# OnePhase_MainPower.net
KiCad netlist of a schematic drawn in Altium Designer
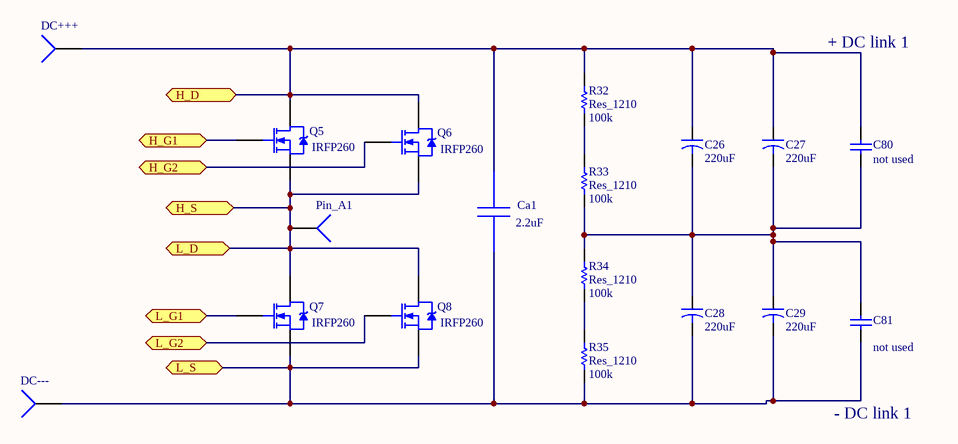
[diagram p0: OnePhase_MainPower.SchDoc]

(export (version "E")
  (design (tool "Eeschema 10.0.6"))
  (components
    (comp (ref "C26")
      (value "220uF")
      (footprint "Capacitor Eletrolitico - duplicate")
      (description "Capacitor")
      (fields (field (name "Comment") "Cap2"))
      (libsource (lib "Miscellaneous Devices") (part "Cap2"))
    )
    (comp (ref "C27")
      (value "220uF")
      (footprint "Capacitor Eletrolitico - duplicate")
      (description "Capacitor")
      (fields (field (name "Comment") "Cap2"))
      (libsource (lib "Miscellaneous Devices") (part "Cap2"))
    )
    (comp (ref "C28")
      (value "220uF")
      (footprint "Capacitor Eletrolitico - duplicate")
      (description "Capacitor")
      (fields (field (name "Comment") "Cap2"))
      (libsource (lib "Miscellaneous Devices") (part "Cap2"))
    )
    (comp (ref "C29")
      (value "220uF")
      (footprint "Capacitor Eletrolitico - duplicate")
      (description "Capacitor")
      (fields (field (name "Comment") "Cap2"))
      (libsource (lib "Miscellaneous Devices") (part "Cap2"))
    )
    (comp (ref "C80")
      (value "not used")
      (footprint "Capacitor_Pol_15x6mm")
      (description "Capacitor")
      (libsource (lib "Miscellaneous Devices") (part "Cap"))
    )
    (comp (ref "C81")
      (value "not used")
      (footprint "Capacitor_Pol_15x6mm")
      (description "Capacitor")
      (libsource (lib "Miscellaneous Devices") (part "Cap"))
    )
    (comp (ref "Ca1")
      (value "2.2uF")
      (footprint "Capacitor_Pol_2Sizes")
      (description "GRM21BC81E475KA1")
      (libsource (lib "TI WEBENCH") (part "Cout"))
    )
    (comp (ref "DC+++")
      (value "Socket")
      (footprint "Power conector")
      (libsource (lib "Miscellaneous Connectors") (part "Socket"))
    )
    (comp (ref "DC---")
      (value "Socket")
      (footprint "Power conector")
      (libsource (lib "Miscellaneous Connectors") (part "Socket"))
    )
    (comp (ref "Pin_A1")
      (value "Socket")
      (footprint "Power conector")
      (libsource (lib "Miscellaneous Connectors") (part "Socket"))
    )
    (comp (ref "Q5")
      (value "IRFP260")
      (footprint "TO227")
      (description "HEXFET Power MOSFET")
      (libsource (lib "IR Discrete MOSFET - Power") (part "IRFP260"))
    )
    (comp (ref "Q6")
      (value "IRFP260")
      (footprint "TO227")
      (description "HEXFET Power MOSFET")
      (libsource (lib "IR Discrete MOSFET - Power") (part "IRFP260"))
    )
    (comp (ref "Q7")
      (value "IRFP260")
      (footprint "TO227")
      (description "HEXFET Power MOSFET")
      (libsource (lib "IR Discrete MOSFET - Power") (part "IRFP260"))
    )
    (comp (ref "Q8")
      (value "IRFP260")
      (footprint "TO227")
      (description "HEXFET Power MOSFET")
      (libsource (lib "IR Discrete MOSFET - Power") (part "IRFP260"))
    )
    (comp (ref "R32")
      (value "Res_1210")
      (footprint "1210_W")
      (description "Resistor")
      (fields (field (name "ALTIUM_VALUE") "100k"))
      (libsource (lib "Inversor_LCEE") (part "Res_0805"))
    )
    (comp (ref "R33")
      (value "Res_1210")
      (footprint "1210_W")
      (description "Resistor")
      (fields (field (name "ALTIUM_VALUE") "100k"))
      (libsource (lib "Inversor_LCEE") (part "Res_0805"))
    )
    (comp (ref "R34")
      (value "Res_1210")
      (footprint "1210_W")
      (description "Resistor")
      (fields (field (name "ALTIUM_VALUE") "100k"))
      (libsource (lib "Inversor_LCEE") (part "Res_0805"))
    )
    (comp (ref "R35")
      (value "Res_1210")
      (footprint "1210_W")
      (description "Resistor")
      (fields (field (name "ALTIUM_VALUE") "100k"))
      (libsource (lib "Inversor_LCEE") (part "Res_0805"))
    )
  )
  (nets
    (net (code "1") (name "/H_D") (class "Default")
      (node (ref "C26") (pin "1") (pinfunction "1_1") (pintype "passive"))
      (node (ref "C27") (pin "1") (pinfunction "1_1") (pintype "passive"))
      (node (ref "C80") (pin "2") (pinfunction "2_2") (pintype "passive"))
      (node (ref "Ca1") (pin "1") (pinfunction "1_1") (pintype "passive"))
      (node (ref "DC+++") (pin "1") (pinfunction "1_1") (pintype "passive"))
      (node (ref "Q5") (pin "2") (pinfunction "D_2") (pintype "passive"))
      (node (ref "Q6") (pin "2") (pinfunction "D_2") (pintype "passive"))
      (node (ref "R32") (pin "1") (pinfunction "1_1") (pintype "passive"))
    )
    (net (code "2") (name "/H_G1") (class "Default")
      (node (ref "Q5") (pin "1") (pinfunction "G_1") (pintype "passive"))
    )
    (net (code "3") (name "/H_G2") (class "Default")
      (node (ref "Q6") (pin "1") (pinfunction "G_1") (pintype "passive"))
    )
    (net (code "4") (name "/H_S") (class "Default")
      (node (ref "Pin_A1") (pin "1") (pinfunction "1_1") (pintype "passive"))
      (node (ref "Q5") (pin "3") (pinfunction "S_3") (pintype "passive"))
      (node (ref "Q6") (pin "3") (pinfunction "S_3") (pintype "passive"))
      (node (ref "Q7") (pin "2") (pinfunction "D_2") (pintype "passive"))
      (node (ref "Q8") (pin "2") (pinfunction "D_2") (pintype "passive"))
    )
    (net (code "5") (name "/L_G1") (class "Default")
      (node (ref "Q7") (pin "1") (pinfunction "G_1") (pintype "passive"))
    )
    (net (code "6") (name "/L_G2") (class "Default")
      (node (ref "Q8") (pin "1") (pinfunction "G_1") (pintype "passive"))
    )
    (net (code "7") (name "/L_S") (class "Default")
      (node (ref "C28") (pin "2") (pinfunction "2_2") (pintype "passive"))
      (node (ref "C29") (pin "2") (pinfunction "2_2") (pintype "passive"))
      (node (ref "C81") (pin "1") (pinfunction "1_1") (pintype "passive"))
      (node (ref "Ca1") (pin "2") (pinfunction "2_2") (pintype "passive"))
      (node (ref "DC---") (pin "1") (pinfunction "1_1") (pintype "passive"))
      (node (ref "Q7") (pin "3") (pinfunction "S_3") (pintype "passive"))
      (node (ref "Q8") (pin "3") (pinfunction "S_3") (pintype "passive"))
      (node (ref "R35") (pin "2") (pinfunction "2_2") (pintype "passive"))
    )
    (net (code "8") (name "Net-(C26-Pad2)") (class "Default")
      (node (ref "C26") (pin "2") (pinfunction "2_2") (pintype "passive"))
      (node (ref "C27") (pin "2") (pinfunction "2_2") (pintype "passive"))
      (node (ref "C28") (pin "1") (pinfunction "1_1") (pintype "passive"))
      (node (ref "C29") (pin "1") (pinfunction "1_1") (pintype "passive"))
      (node (ref "C80") (pin "1") (pinfunction "1_1") (pintype "passive"))
      (node (ref "C81") (pin "2") (pinfunction "2_2") (pintype "passive"))
      (node (ref "R33") (pin "2") (pinfunction "2_2") (pintype "passive"))
      (node (ref "R34") (pin "1") (pinfunction "1_1") (pintype "passive"))
    )
    (net (code "9") (name "Net-(R32-Pad2)") (class "Default")
      (node (ref "R32") (pin "2") (pinfunction "2_2") (pintype "passive"))
      (node (ref "R33") (pin "1") (pinfunction "1_1") (pintype "passive"))
    )
    (net (code "10") (name "Net-(R34-Pad2)") (class "Default")
      (node (ref "R34") (pin "2") (pinfunction "2_2") (pintype "passive"))
      (node (ref "R35") (pin "1") (pinfunction "1_1") (pintype "passive"))
    )
  )
)
